# Rotary_Encoder.net
KiCad netlist of a schematic drawn in Altium Designer
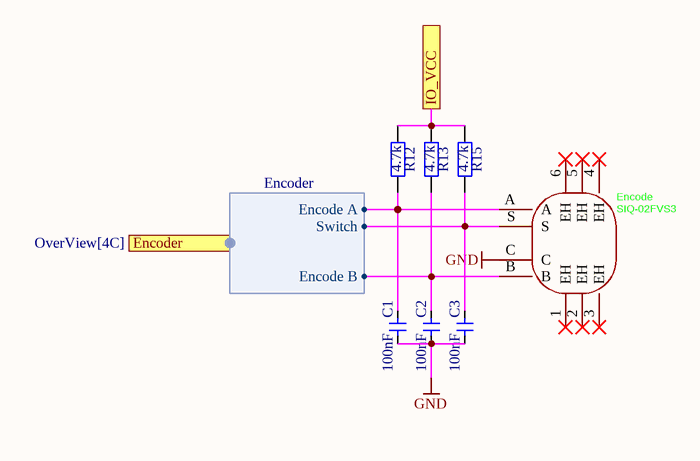
[diagram p0: Rotary Encoder.SchDoc]

(export (version "E")
  (design (tool "Eeschema 10.0.6"))
  (components
    (comp (ref "C1")
      (value "100nF")
      (footprint "0402-C")
      (description "Capacitor")
      (libsource (lib "MyPcbLib") (part "电容-0402"))
    )
    (comp (ref "C2")
      (value "100nF")
      (footprint "0402-C")
      (description "Capacitor")
      (libsource (lib "MyPcbLib") (part "电容-0402"))
    )
    (comp (ref "C3")
      (value "100nF")
      (footprint "0402-C")
      (description "Capacitor")
      (libsource (lib "MyPcbLib") (part "电容-0402"))
    )
    (comp (ref "Encode")
      (value "SIQ-02FVS3")
      (footprint "SW-SMD_SIQ-02FVS3_1")
      (fields (field (name "MANUFACTURER") "MITSUMI(美上美)"))
      (libsource (lib "MyLib") (part "SIQ-02FVS3"))
    )
    (comp (ref "R12")
      (value "4.7k")
      (footprint "0402-R")
      (description "贴片电阻")
      (libsource (lib "0.1 - 电阻-电容-电感-保险丝-晶振-晶体-磁珠-电位器-法拉电容-馈通电容") (part "R"))
    )
    (comp (ref "R13")
      (value "4.7k")
      (footprint "0402-R")
      (description "贴片电阻")
      (libsource (lib "0.1 - 电阻-电容-电感-保险丝-晶振-晶体-磁珠-电位器-法拉电容-馈通电容") (part "R"))
    )
    (comp (ref "R15")
      (value "4.7k")
      (footprint "0402-R")
      (description "贴片电阻")
      (libsource (lib "0.1 - 电阻-电容-电感-保险丝-晶振-晶体-磁珠-电位器-法拉电容-馈通电容") (part "R"))
    )
  )
  (nets
    (net (code "2") (name "/IO_VCC") (class "Default")
      (node (ref "R12") (pin "2") (pinfunction "2_2") (pintype "passive"))
      (node (ref "R13") (pin "2") (pinfunction "2_2") (pintype "passive"))
      (node (ref "R15") (pin "2") (pinfunction "2_2") (pintype "passive"))
    )
    (net (code "4") (name "GND") (class "Default")
      (node (ref "C1") (pin "2") (pinfunction "2_2") (pintype "passive"))
      (node (ref "C2") (pin "2") (pinfunction "2_2") (pintype "passive"))
      (node (ref "C3") (pin "2") (pinfunction "2_2") (pintype "passive"))
      (node (ref "Encode") (pin "C") (pinfunction "C_C") (pintype "passive"))
    )
    (net (code "5") (name "Net-(C1-Pad1)") (class "Default")
      (node (ref "C1") (pin "1") (pinfunction "1_1") (pintype "passive"))
      (node (ref "Encode") (pin "A") (pinfunction "A_A") (pintype "passive"))
      (node (ref "R12") (pin "1") (pinfunction "1_1") (pintype "passive"))
    )
    (net (code "6") (name "Net-(C2-Pad1)") (class "Default")
      (node (ref "C2") (pin "1") (pinfunction "1_1") (pintype "passive"))
      (node (ref "Encode") (pin "B") (pinfunction "B_B") (pintype "passive"))
      (node (ref "R13") (pin "1") (pinfunction "1_1") (pintype "passive"))
    )
    (net (code "7") (name "Net-(C3-Pad1)") (class "Default")
      (node (ref "C3") (pin "1") (pinfunction "1_1") (pintype "passive"))
      (node (ref "Encode") (pin "S") (pinfunction "S_S") (pintype "passive"))
      (node (ref "R15") (pin "1") (pinfunction "1_1") (pintype "passive"))
    )
    (net (code "8") (name "unconnected-(Encode-EH-Pad1)") (class "Default")
      (node (ref "Encode") (pin "1") (pinfunction "EH_1") (pintype "passive+no_connect"))
    )
    (net (code "9") (name "unconnected-(Encode-EH-Pad2)") (class "Default")
      (node (ref "Encode") (pin "2") (pinfunction "EH_2") (pintype "passive+no_connect"))
    )
    (net (code "10") (name "unconnected-(Encode-EH-Pad3)") (class "Default")
      (node (ref "Encode") (pin "3") (pinfunction "EH_3") (pintype "passive+no_connect"))
    )
    (net (code "11") (name "unconnected-(Encode-EH-Pad4)") (class "Default")
      (node (ref "Encode") (pin "4") (pinfunction "EH_4") (pintype "passive+no_connect"))
    )
    (net (code "12") (name "unconnected-(Encode-EH-Pad5)") (class "Default")
      (node (ref "Encode") (pin "5") (pinfunction "EH_5") (pintype "passive+no_connect"))
    )
    (net (code "13") (name "unconnected-(Encode-EH-Pad6)") (class "Default")
      (node (ref "Encode") (pin "6") (pinfunction "EH_6") (pintype "passive+no_connect"))
    )
  )
)
